# sp6641b.net
KiCad netlist of a schematic drawn in EAGLE
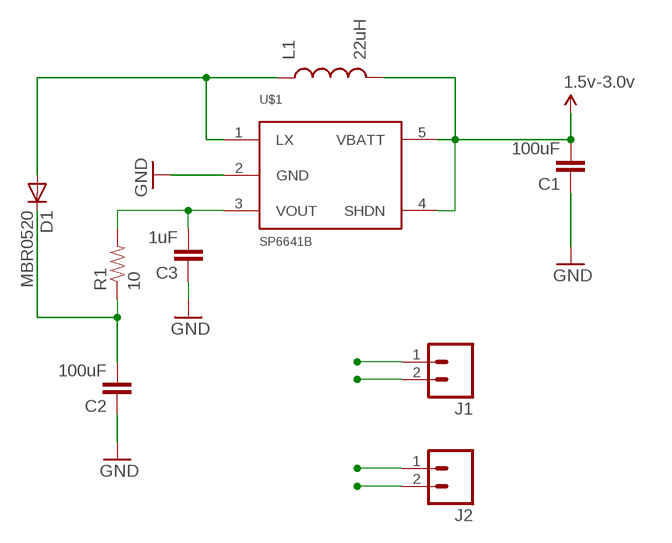
[diagram p0: schematic, sheet 1]

(export (version "E")
  (design (tool "Eeschema 10.0.6"))
  (components
    (comp (ref "C1")
      (value "100uF")
      (footprint "eagle-import:0805")
      (libsource (lib "eagle-import") (part "CAP0805"))
    )
    (comp (ref "C2")
      (value "100uF")
      (footprint "eagle-import:0805")
      (libsource (lib "eagle-import") (part "CAP0805"))
    )
    (comp (ref "C3")
      (value "1uF")
      (footprint "eagle-import:0805")
      (libsource (lib "eagle-import") (part "CAP0805"))
    )
    (comp (ref "D1")
      (value "MBR0520")
      (footprint "eagle-import:SOD123")
      (libsource (lib "eagle-import") (part "MBR0520LT"))
    )
    (comp (ref "J1")
      (value "M02PTH")
      (footprint "eagle-import:1X02")
      (libsource (lib "eagle-import") (part "M02PTH"))
    )
    (comp (ref "J2")
      (value "M02PTH")
      (footprint "eagle-import:1X02")
      (libsource (lib "eagle-import") (part "M02PTH"))
    )
    (comp (ref "L1")
      (value "22uH")
      (footprint "eagle-import:CR54")
      (libsource (lib "eagle-import") (part "INDUCTORCR54"))
    )
    (comp (ref "R1")
      (value "10")
      (footprint "eagle-import:0805")
      (libsource (lib "eagle-import") (part "0.3OHM-1/8W-1%(0805)"))
    )
    (comp (ref "U$1")
      (value "SP6641B")
      (footprint "eagle-import:SOT23-5")
      (libsource (lib "eagle-import") (part "SP6641SP6641A/B"))
    )
  )
  (nets
    (net (code "1") (name "/VOUT") (class "Default")
      (node (ref "C2") (pin "2") (pinfunction "2_2") (pintype "passive"))
      (node (ref "D1") (pin "C") (pinfunction "C_C") (pintype "passive"))
      (node (ref "J2") (pin "1") (pinfunction "1_1") (pintype "passive"))
      (node (ref "R1") (pin "1") (pinfunction "1_1") (pintype "passive"))
    )
    (net (code "2") (name "1.5v-3.0v") (class "Default")
      (node (ref "C1") (pin "2") (pinfunction "2_2") (pintype "passive"))
      (node (ref "J1") (pin "1") (pinfunction "1_1") (pintype "passive"))
      (node (ref "L1") (pin "P$2") (pinfunction "2_P$2") (pintype "passive"))
      (node (ref "U$1") (pin "4") (pinfunction "SHDN_4") (pintype "bidirectional"))
      (node (ref "U$1") (pin "5") (pinfunction "VBATT_5") (pintype "bidirectional"))
    )
    (net (code "3") (name "GND") (class "Default")
      (node (ref "C1") (pin "1") (pinfunction "1_1") (pintype "passive"))
      (node (ref "C2") (pin "1") (pinfunction "1_1") (pintype "passive"))
      (node (ref "C3") (pin "1") (pinfunction "1_1") (pintype "passive"))
      (node (ref "J1") (pin "2") (pinfunction "2_2") (pintype "passive"))
      (node (ref "J2") (pin "2") (pinfunction "2_2") (pintype "passive"))
      (node (ref "U$1") (pin "2") (pinfunction "GND_2") (pintype "bidirectional"))
    )
    (net (code "4") (name "Net-(L1-1)") (class "Default")
      (node (ref "D1") (pin "A") (pinfunction "A_A") (pintype "passive"))
      (node (ref "L1") (pin "P$1") (pinfunction "1_P$1") (pintype "passive"))
      (node (ref "U$1") (pin "1") (pinfunction "LX_1") (pintype "bidirectional"))
    )
    (net (code "5") (name "Net-(U$1-VOUT)") (class "Default")
      (node (ref "C3") (pin "2") (pinfunction "2_2") (pintype "passive"))
      (node (ref "R1") (pin "2") (pinfunction "2_2") (pintype "passive"))
      (node (ref "U$1") (pin "3") (pinfunction "VOUT_3") (pintype "bidirectional"))
    )
  )
)
